# ATmga8_testBoard_v4.net
KiCad netlist of a schematic drawn in EAGLE
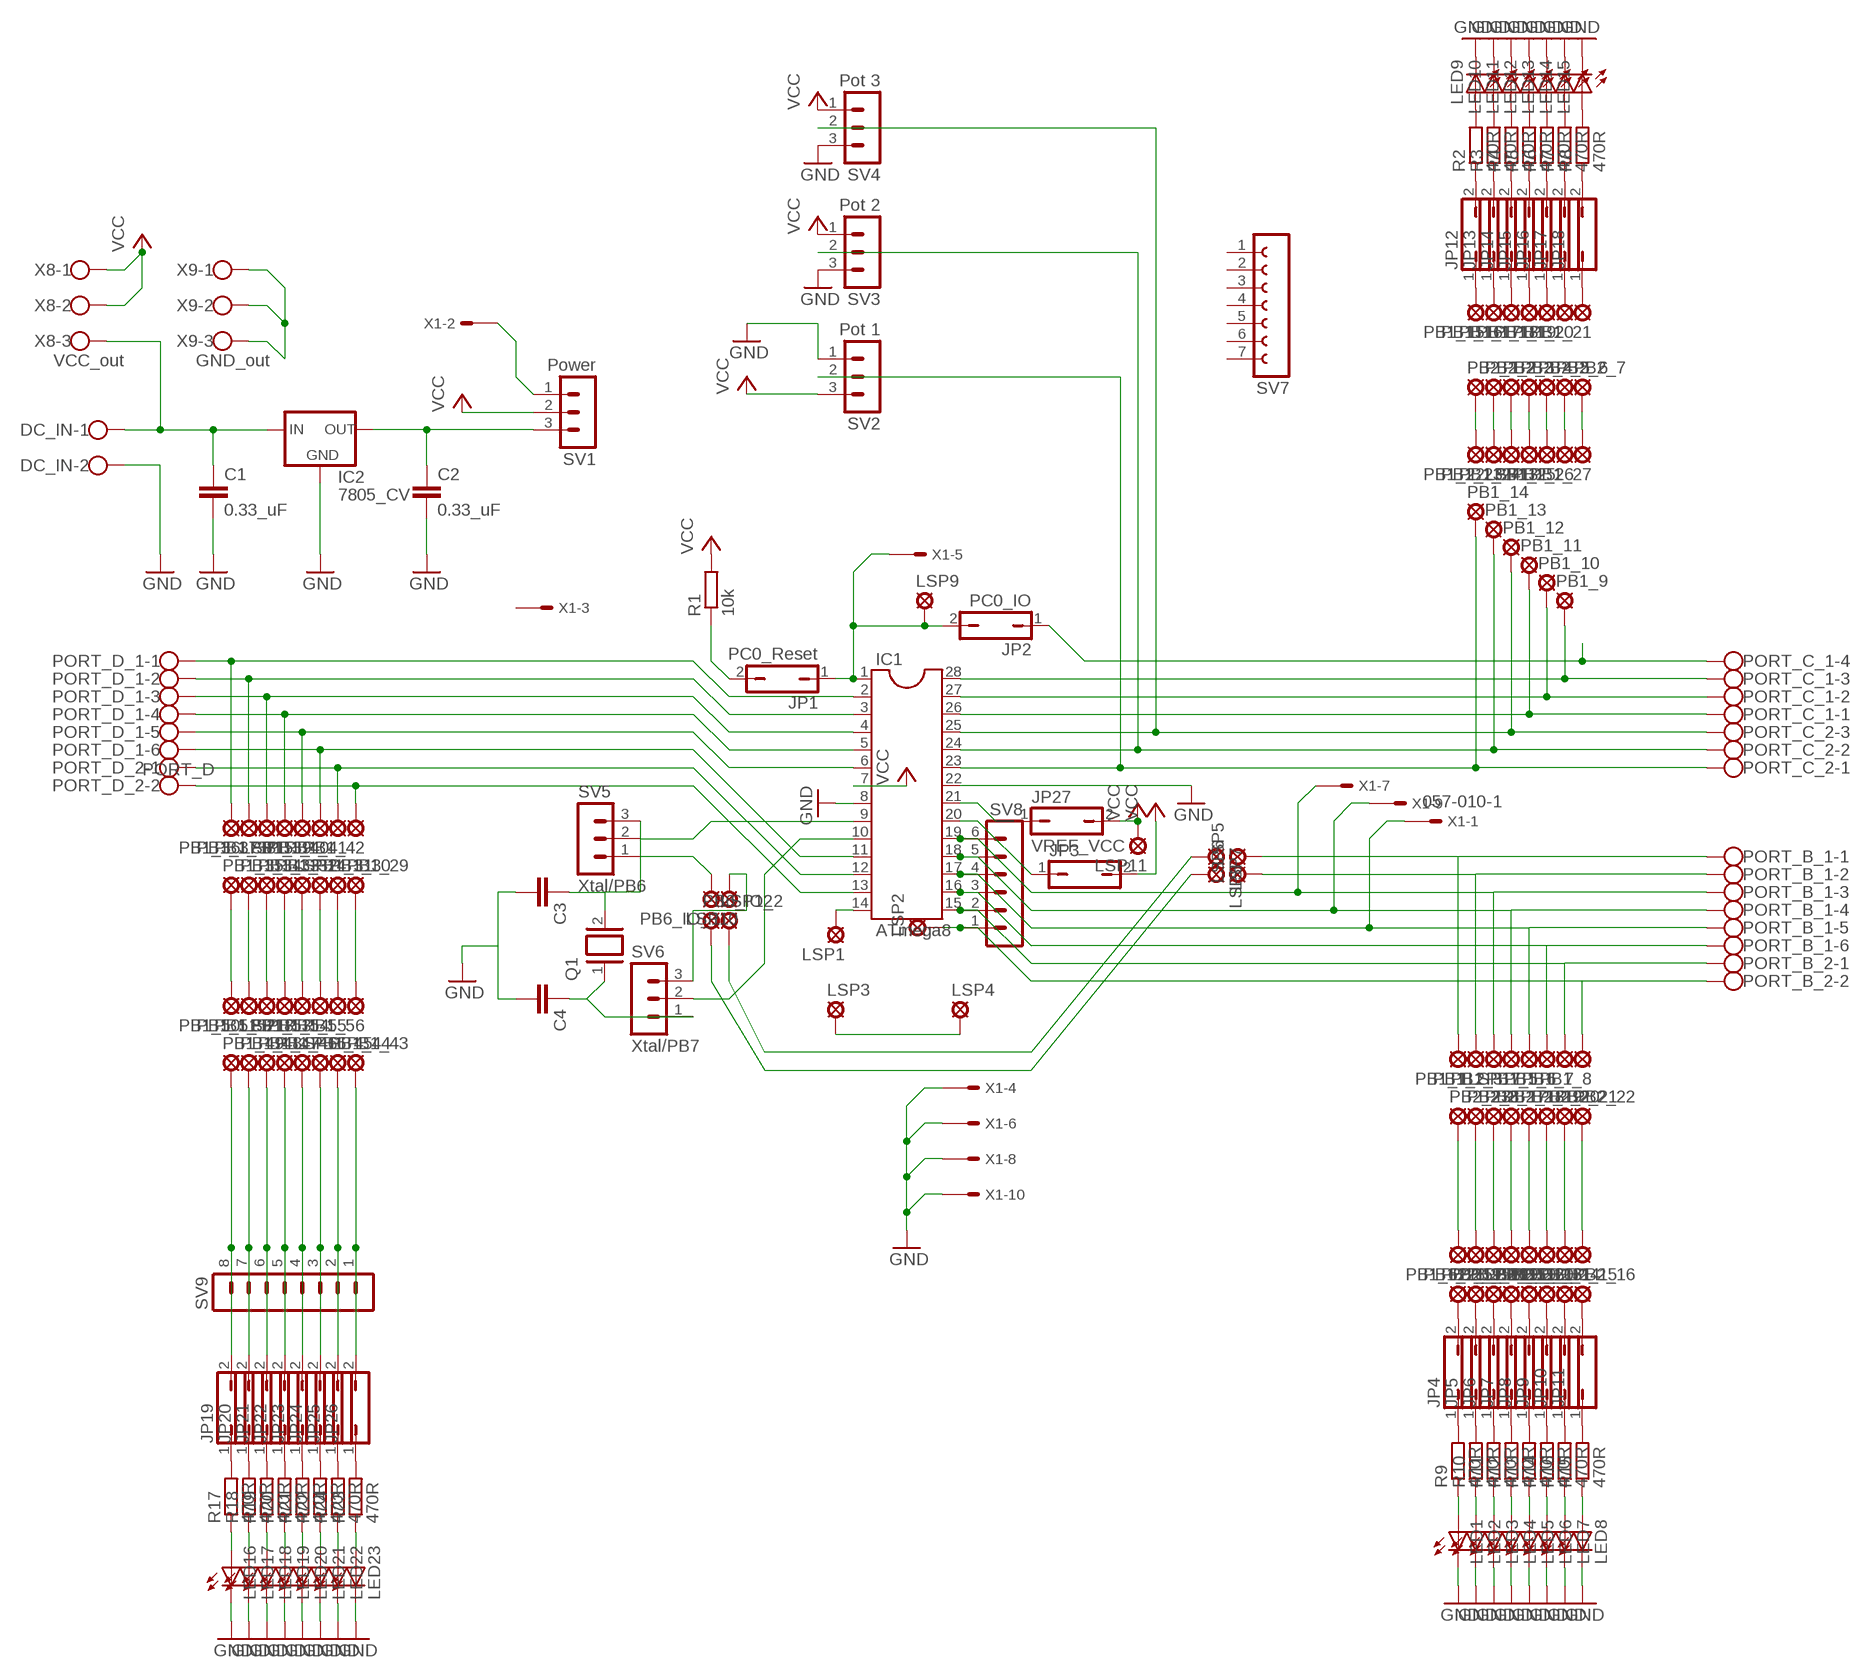
[diagram p0: schematic, sheet 1]

(export (version "E")
  (design (tool "Eeschema 10.0.6"))
  (components
    (comp (ref "C1")
      (value "0.33_uF")
      (footprint "eagle-import:C5B2.5")
      (libsource (lib "eagle-import") (part "C5/2.5"))
    )
    (comp (ref "C2")
      (value "0.33_uF")
      (footprint "eagle-import:C5B2.5")
      (libsource (lib "eagle-import") (part "C5/2.5"))
    )
    (comp (ref "C3")
      (value "C-EU025-024X044")
      (footprint "eagle-import:C025-024X044")
      (libsource (lib "eagle-import") (part "C-EU025-024X044"))
    )
    (comp (ref "C4")
      (value "C-EU025-024X044")
      (footprint "eagle-import:C025-024X044")
      (libsource (lib "eagle-import") (part "C-EU025-024X044"))
    )
    (comp (ref "DC_IN")
      (value "W237-102")
      (footprint "eagle-import:W237-102")
      (fields (field (name "MPN") "237-102"))
      (libsource (lib "eagle-import") (part "W237-102"))
    )
    (comp (ref "IC1")
      (value "ATmega8")
      (footprint "eagle-import:DIL28-3")
      (libsource (lib "eagle-import") (part "DIL28-3"))
    )
    (comp (ref "IC2")
      (value "7805_CV")
      (footprint "eagle-import:78XXS")
      (libsource (lib "eagle-import") (part "78XXS"))
    )
    (comp (ref "JP1")
      (value "PC0_Reset")
      (footprint "eagle-import:JP1")
      (libsource (lib "eagle-import") (part "JP1Q"))
    )
    (comp (ref "JP2")
      (value "PC0_IO")
      (footprint "eagle-import:JP1")
      (libsource (lib "eagle-import") (part "JP1Q"))
    )
    (comp (ref "JP3")
      (value "JP1Q")
      (footprint "eagle-import:JP1")
      (libsource (lib "eagle-import") (part "JP1Q"))
    )
    (comp (ref "JP4")
      (value "JP1Q")
      (footprint "eagle-import:JP1")
      (libsource (lib "eagle-import") (part "JP1Q"))
    )
    (comp (ref "JP5")
      (value "JP1Q")
      (footprint "eagle-import:JP1")
      (libsource (lib "eagle-import") (part "JP1Q"))
    )
    (comp (ref "JP6")
      (value "JP1Q")
      (footprint "eagle-import:JP1")
      (libsource (lib "eagle-import") (part "JP1Q"))
    )
    (comp (ref "JP7")
      (value "JP1Q")
      (footprint "eagle-import:JP1")
      (libsource (lib "eagle-import") (part "JP1Q"))
    )
    (comp (ref "JP8")
      (value "JP1Q")
      (footprint "eagle-import:JP1")
      (libsource (lib "eagle-import") (part "JP1Q"))
    )
    (comp (ref "JP9")
      (value "JP1Q")
      (footprint "eagle-import:JP1")
      (libsource (lib "eagle-import") (part "JP1Q"))
    )
    (comp (ref "JP10")
      (value "JP1Q")
      (footprint "eagle-import:JP1")
      (libsource (lib "eagle-import") (part "JP1Q"))
    )
    (comp (ref "JP11")
      (value "JP1Q")
      (footprint "eagle-import:JP1")
      (libsource (lib "eagle-import") (part "JP1Q"))
    )
    (comp (ref "JP12")
      (value "JP1Q")
      (footprint "eagle-import:JP1")
      (libsource (lib "eagle-import") (part "JP1Q"))
    )
    (comp (ref "JP13")
      (value "JP1Q")
      (footprint "eagle-import:JP1")
      (libsource (lib "eagle-import") (part "JP1Q"))
    )
    (comp (ref "JP14")
      (value "JP1Q")
      (footprint "eagle-import:JP1")
      (libsource (lib "eagle-import") (part "JP1Q"))
    )
    (comp (ref "JP15")
      (value "JP1Q")
      (footprint "eagle-import:JP1")
      (libsource (lib "eagle-import") (part "JP1Q"))
    )
    (comp (ref "JP16")
      (value "JP1Q")
      (footprint "eagle-import:JP1")
      (libsource (lib "eagle-import") (part "JP1Q"))
    )
    (comp (ref "JP17")
      (value "JP1Q")
      (footprint "eagle-import:JP1")
      (libsource (lib "eagle-import") (part "JP1Q"))
    )
    (comp (ref "JP18")
      (value "JP1Q")
      (footprint "eagle-import:JP1")
      (libsource (lib "eagle-import") (part "JP1Q"))
    )
    (comp (ref "JP19")
      (value "JP1Q")
      (footprint "eagle-import:JP1")
      (libsource (lib "eagle-import") (part "JP1Q"))
    )
    (comp (ref "JP20")
      (value "JP1Q")
      (footprint "eagle-import:JP1")
      (libsource (lib "eagle-import") (part "JP1Q"))
    )
    (comp (ref "JP21")
      (value "JP1Q")
      (footprint "eagle-import:JP1")
      (libsource (lib "eagle-import") (part "JP1Q"))
    )
    (comp (ref "JP22")
      (value "JP1Q")
      (footprint "eagle-import:JP1")
      (libsource (lib "eagle-import") (part "JP1Q"))
    )
    (comp (ref "JP23")
      (value "JP1Q")
      (footprint "eagle-import:JP1")
      (libsource (lib "eagle-import") (part "JP1Q"))
    )
    (comp (ref "JP24")
      (value "JP1Q")
      (footprint "eagle-import:JP1")
      (libsource (lib "eagle-import") (part "JP1Q"))
    )
    (comp (ref "JP25")
      (value "JP1Q")
      (footprint "eagle-import:JP1")
      (libsource (lib "eagle-import") (part "JP1Q"))
    )
    (comp (ref "JP26")
      (value "JP1Q")
      (footprint "eagle-import:JP1")
      (libsource (lib "eagle-import") (part "JP1Q"))
    )
    (comp (ref "JP27")
      (value "VREF_VCC")
      (footprint "eagle-import:JP1")
      (libsource (lib "eagle-import") (part "JP1Q"))
    )
    (comp (ref "LED1")
      (value "LED3MM")
      (footprint "eagle-import:LED3MM")
      (libsource (lib "eagle-import") (part "LED3MM"))
    )
    (comp (ref "LED2")
      (value "LED3MM")
      (footprint "eagle-import:LED3MM")
      (libsource (lib "eagle-import") (part "LED3MM"))
    )
    (comp (ref "LED3")
      (value "LED3MM")
      (footprint "eagle-import:LED3MM")
      (libsource (lib "eagle-import") (part "LED3MM"))
    )
    (comp (ref "LED4")
      (value "LED3MM")
      (footprint "eagle-import:LED3MM")
      (libsource (lib "eagle-import") (part "LED3MM"))
    )
    (comp (ref "LED5")
      (value "LED3MM")
      (footprint "eagle-import:LED3MM")
      (libsource (lib "eagle-import") (part "LED3MM"))
    )
    (comp (ref "LED6")
      (value "LED3MM")
      (footprint "eagle-import:LED3MM")
      (libsource (lib "eagle-import") (part "LED3MM"))
    )
    (comp (ref "LED7")
      (value "LED3MM")
      (footprint "eagle-import:LED3MM")
      (libsource (lib "eagle-import") (part "LED3MM"))
    )
    (comp (ref "LED8")
      (value "LED3MM")
      (footprint "eagle-import:LED3MM")
      (libsource (lib "eagle-import") (part "LED3MM"))
    )
    (comp (ref "LED9")
      (value "LED3MM")
      (footprint "eagle-import:LED3MM")
      (libsource (lib "eagle-import") (part "LED3MM"))
    )
    (comp (ref "LED10")
      (value "LED3MM")
      (footprint "eagle-import:LED3MM")
      (libsource (lib "eagle-import") (part "LED3MM"))
    )
    (comp (ref "LED11")
      (value "LED3MM")
      (footprint "eagle-import:LED3MM")
      (libsource (lib "eagle-import") (part "LED3MM"))
    )
    (comp (ref "LED12")
      (value "LED3MM")
      (footprint "eagle-import:LED3MM")
      (libsource (lib "eagle-import") (part "LED3MM"))
    )
    (comp (ref "LED13")
      (value "LED3MM")
      (footprint "eagle-import:LED3MM")
      (libsource (lib "eagle-import") (part "LED3MM"))
    )
    (comp (ref "LED14")
      (value "LED3MM")
      (footprint "eagle-import:LED3MM")
      (libsource (lib "eagle-import") (part "LED3MM"))
    )
    (comp (ref "LED15")
      (value "LED3MM")
      (footprint "eagle-import:LED3MM")
      (libsource (lib "eagle-import") (part "LED3MM"))
    )
    (comp (ref "LED16")
      (value "LED3MM")
      (footprint "eagle-import:LED3MM")
      (libsource (lib "eagle-import") (part "LED3MM"))
    )
    (comp (ref "LED17")
      (value "LED3MM")
      (footprint "eagle-import:LED3MM")
      (libsource (lib "eagle-import") (part "LED3MM"))
    )
    (comp (ref "LED18")
      (value "LED3MM")
      (footprint "eagle-import:LED3MM")
      (libsource (lib "eagle-import") (part "LED3MM"))
    )
    (comp (ref "LED19")
      (value "LED3MM")
      (footprint "eagle-import:LED3MM")
      (libsource (lib "eagle-import") (part "LED3MM"))
    )
    (comp (ref "LED20")
      (value "LED3MM")
      (footprint "eagle-import:LED3MM")
      (libsource (lib "eagle-import") (part "LED3MM"))
    )
    (comp (ref "LED21")
      (value "LED3MM")
      (footprint "eagle-import:LED3MM")
      (libsource (lib "eagle-import") (part "LED3MM"))
    )
    (comp (ref "LED22")
      (value "LED3MM")
      (footprint "eagle-import:LED3MM")
      (libsource (lib "eagle-import") (part "LED3MM"))
    )
    (comp (ref "LED23")
      (value "LED3MM")
      (footprint "eagle-import:LED3MM")
      (libsource (lib "eagle-import") (part "LED3MM"))
    )
    (comp (ref "LSP1")
      (value "LSP10")
      (footprint "eagle-import:LSP10")
      (libsource (lib "eagle-import") (part "LSP10"))
    )
    (comp (ref "LSP2")
      (value "LSP10")
      (footprint "eagle-import:LSP10")
      (libsource (lib "eagle-import") (part "LSP10"))
    )
    (comp (ref "LSP3")
      (value "LSP10")
      (footprint "eagle-import:LSP10")
      (libsource (lib "eagle-import") (part "LSP10"))
    )
    (comp (ref "LSP4")
      (value "LSP10")
      (footprint "eagle-import:LSP10")
      (libsource (lib "eagle-import") (part "LSP10"))
    )
    (comp (ref "LSP5")
      (value "LSP10")
      (footprint "eagle-import:LSP10")
      (libsource (lib "eagle-import") (part "LSP10"))
    )
    (comp (ref "LSP6")
      (value "LSP10")
      (footprint "eagle-import:LSP10")
      (libsource (lib "eagle-import") (part "LSP10"))
    )
    (comp (ref "LSP7")
      (value "LSP10")
      (footprint "eagle-import:LSP10")
      (libsource (lib "eagle-import") (part "LSP10"))
    )
    (comp (ref "LSP8")
      (value "LSP10")
      (footprint "eagle-import:LSP10")
      (libsource (lib "eagle-import") (part "LSP10"))
    )
    (comp (ref "LSP9")
      (value "LSP10")
      (footprint "eagle-import:LSP10")
      (libsource (lib "eagle-import") (part "LSP10"))
    )
    (comp (ref "LSP10")
      (value "LSP10")
      (footprint "eagle-import:LSP10")
      (libsource (lib "eagle-import") (part "LSP10"))
    )
    (comp (ref "LSP11")
      (value "LSP10")
      (footprint "eagle-import:LSP10")
      (libsource (lib "eagle-import") (part "LSP10"))
    )
    (comp (ref "LSP12")
      (value "LSP10")
      (footprint "eagle-import:LSP10")
      (libsource (lib "eagle-import") (part "LSP10"))
    )
    (comp (ref "LSP13")
      (value "LSP10")
      (footprint "eagle-import:LSP10")
      (libsource (lib "eagle-import") (part "LSP10"))
    )
    (comp (ref "LSP14")
      (value "LSP10")
      (footprint "eagle-import:LSP10")
      (libsource (lib "eagle-import") (part "LSP10"))
    )
    (comp (ref "LSP15")
      (value "LSP10")
      (footprint "eagle-import:LSP10")
      (libsource (lib "eagle-import") (part "LSP10"))
    )
    (comp (ref "LSP16")
      (value "LSP10")
      (footprint "eagle-import:LSP10")
      (libsource (lib "eagle-import") (part "LSP10"))
    )
    (comp (ref "LSP17")
      (value "LSP10")
      (footprint "eagle-import:LSP10")
      (libsource (lib "eagle-import") (part "LSP10"))
    )
    (comp (ref "LSP18")
      (value "LSP10")
      (footprint "eagle-import:LSP10")
      (libsource (lib "eagle-import") (part "LSP10"))
    )
    (comp (ref "LSP19")
      (value "LSP10")
      (footprint "eagle-import:LSP10")
      (libsource (lib "eagle-import") (part "LSP10"))
    )
    (comp (ref "PB1_1")
      (value "LSP10")
      (footprint "eagle-import:LSP10")
      (libsource (lib "eagle-import") (part "LSP10"))
    )
    (comp (ref "PB1_2")
      (value "LSP10")
      (footprint "eagle-import:LSP10")
      (libsource (lib "eagle-import") (part "LSP10"))
    )
    (comp (ref "PB1_3")
      (value "LSP10")
      (footprint "eagle-import:LSP10")
      (libsource (lib "eagle-import") (part "LSP10"))
    )
    (comp (ref "PB1_5")
      (value "LSP10")
      (footprint "eagle-import:LSP10")
      (libsource (lib "eagle-import") (part "LSP10"))
    )
    (comp (ref "PB1_6")
      (value "LSP10")
      (footprint "eagle-import:LSP10")
      (libsource (lib "eagle-import") (part "LSP10"))
    )
    (comp (ref "PB1_7")
      (value "LSP10")
      (footprint "eagle-import:LSP10")
      (libsource (lib "eagle-import") (part "LSP10"))
    )
    (comp (ref "PB1_8")
      (value "LSP10")
      (footprint "eagle-import:LSP10")
      (libsource (lib "eagle-import") (part "LSP10"))
    )
    (comp (ref "PB1_9")
      (value "LSP10")
      (footprint "eagle-import:LSP10")
      (libsource (lib "eagle-import") (part "LSP10"))
    )
    (comp (ref "PB1_10")
      (value "LSP10")
      (footprint "eagle-import:LSP10")
      (libsource (lib "eagle-import") (part "LSP10"))
    )
    (comp (ref "PB1_11")
      (value "LSP10")
      (footprint "eagle-import:LSP10")
      (libsource (lib "eagle-import") (part "LSP10"))
    )
    (comp (ref "PB1_12")
      (value "LSP10")
      (footprint "eagle-import:LSP10")
      (libsource (lib "eagle-import") (part "LSP10"))
    )
    (comp (ref "PB1_13")
      (value "LSP10")
      (footprint "eagle-import:LSP10")
      (libsource (lib "eagle-import") (part "LSP10"))
    )
    (comp (ref "PB1_14")
      (value "LSP10")
      (footprint "eagle-import:LSP10")
      (libsource (lib "eagle-import") (part "LSP10"))
    )
    (comp (ref "PB1_15")
      (value "LSP10")
      (footprint "eagle-import:LSP10")
      (libsource (lib "eagle-import") (part "LSP10"))
    )
    (comp (ref "PB1_16")
      (value "LSP10")
      (footprint "eagle-import:LSP10")
      (libsource (lib "eagle-import") (part "LSP10"))
    )
    (comp (ref "PB1_17")
      (value "LSP10")
      (footprint "eagle-import:LSP10")
      (libsource (lib "eagle-import") (part "LSP10"))
    )
    (comp (ref "PB1_18")
      (value "LSP10")
      (footprint "eagle-import:LSP10")
      (libsource (lib "eagle-import") (part "LSP10"))
    )
    (comp (ref "PB1_19")
      (value "LSP10")
      (footprint "eagle-import:LSP10")
      (libsource (lib "eagle-import") (part "LSP10"))
    )
    (comp (ref "PB1_20")
      (value "LSP10")
      (footprint "eagle-import:LSP10")
      (libsource (lib "eagle-import") (part "LSP10"))
    )
    (comp (ref "PB1_21")
      (value "LSP10")
      (footprint "eagle-import:LSP10")
      (libsource (lib "eagle-import") (part "LSP10"))
    )
    (comp (ref "PB1_22")
      (value "LSP10")
      (footprint "eagle-import:LSP10")
      (libsource (lib "eagle-import") (part "LSP10"))
    )
    (comp (ref "PB1_23")
      (value "LSP10")
      (footprint "eagle-import:LSP10")
      (libsource (lib "eagle-import") (part "LSP10"))
    )
    (comp (ref "PB1_24")
      (value "LSP10")
      (footprint "eagle-import:LSP10")
      (libsource (lib "eagle-import") (part "LSP10"))
    )
    (comp (ref "PB1_25")
      (value "LSP10")
      (footprint "eagle-import:LSP10")
      (libsource (lib "eagle-import") (part "LSP10"))
    )
    (comp (ref "PB1_26")
      (value "LSP10")
      (footprint "eagle-import:LSP10")
      (libsource (lib "eagle-import") (part "LSP10"))
    )
    (comp (ref "PB1_27")
      (value "LSP10")
      (footprint "eagle-import:LSP10")
      (libsource (lib "eagle-import") (part "LSP10"))
    )
    (comp (ref "PB1_28")
      (value "LSP10")
      (footprint "eagle-import:LSP10")
      (libsource (lib "eagle-import") (part "LSP10"))
    )
    (comp (ref "PB1_29")
      (value "LSP10")
      (footprint "eagle-import:LSP10")
      (libsource (lib "eagle-import") (part "LSP10"))
    )
    (comp (ref "PB1_30")
      (value "LSP10")
      (footprint "eagle-import:LSP10")
      (libsource (lib "eagle-import") (part "LSP10"))
    )
    (comp (ref "PB1_31")
      (value "LSP10")
      (footprint "eagle-import:LSP10")
      (libsource (lib "eagle-import") (part "LSP10"))
    )
    (comp (ref "PB1_32")
      (value "LSP10")
      (footprint "eagle-import:LSP10")
      (libsource (lib "eagle-import") (part "LSP10"))
    )
    (comp (ref "PB1_33")
      (value "LSP10")
      (footprint "eagle-import:LSP10")
      (libsource (lib "eagle-import") (part "LSP10"))
    )
    (comp (ref "PB1_34")
      (value "LSP10")
      (footprint "eagle-import:LSP10")
      (libsource (lib "eagle-import") (part "LSP10"))
    )
    (comp (ref "PB1_35")
      (value "LSP10")
      (footprint "eagle-import:LSP10")
      (libsource (lib "eagle-import") (part "LSP10"))
    )
    (comp (ref "PB1_36")
      (value "LSP10")
      (footprint "eagle-import:LSP10")
      (libsource (lib "eagle-import") (part "LSP10"))
    )
    (comp (ref "PB1_37")
      (value "LSP10")
      (footprint "eagle-import:LSP10")
      (libsource (lib "eagle-import") (part "LSP10"))
    )
    (comp (ref "PB1_38")
      (value "LSP10")
      (footprint "eagle-import:LSP10")
      (libsource (lib "eagle-import") (part "LSP10"))
    )
    (comp (ref "PB1_39")
      (value "LSP10")
      (footprint "eagle-import:LSP10")
      (libsource (lib "eagle-import") (part "LSP10"))
    )
    (comp (ref "PB1_40")
      (value "LSP10")
      (footprint "eagle-import:LSP10")
      (libsource (lib "eagle-import") (part "LSP10"))
    )
    (comp (ref "PB1_41")
      (value "LSP10")
      (footprint "eagle-import:LSP10")
      (libsource (lib "eagle-import") (part "LSP10"))
    )
    (comp (ref "PB1_42")
      (value "LSP10")
      (footprint "eagle-import:LSP10")
      (libsource (lib "eagle-import") (part "LSP10"))
    )
    (comp (ref "PB1_43")
      (value "LSP10")
      (footprint "eagle-import:LSP10")
      (libsource (lib "eagle-import") (part "LSP10"))
    )
    (comp (ref "PB1_44")
      (value "LSP10")
      (footprint "eagle-import:LSP10")
      (libsource (lib "eagle-import") (part "LSP10"))
    )
    (comp (ref "PB1_45")
      (value "LSP10")
      (footprint "eagle-import:LSP10")
      (libsource (lib "eagle-import") (part "LSP10"))
    )
    (comp (ref "PB1_46")
      (value "LSP10")
      (footprint "eagle-import:LSP10")
      (libsource (lib "eagle-import") (part "LSP10"))
    )
    (comp (ref "PB1_47")
      (value "LSP10")
      (footprint "eagle-import:LSP10")
      (libsource (lib "eagle-import") (part "LSP10"))
    )
    (comp (ref "PB1_48")
      (value "LSP10")
      (footprint "eagle-import:LSP10")
      (libsource (lib "eagle-import") (part "LSP10"))
    )
    (comp (ref "PB1_49")
      (value "LSP10")
      (footprint "eagle-import:LSP10")
      (libsource (lib "eagle-import") (part "LSP10"))
    )
    (comp (ref "PB1_50")
      (value "LSP10")
      (footprint "eagle-import:LSP10")
      (libsource (lib "eagle-import") (part "LSP10"))
    )
    (comp (ref "PB1_51")
      (value "LSP10")
      (footprint "eagle-import:LSP10")
      (libsource (lib "eagle-import") (part "LSP10"))
    )
    (comp (ref "PB1_52")
      (value "LSP10")
      (footprint "eagle-import:LSP10")
      (libsource (lib "eagle-import") (part "LSP10"))
    )
    (comp (ref "PB1_53")
      (value "LSP10")
      (footprint "eagle-import:LSP10")
      (libsource (lib "eagle-import") (part "LSP10"))
    )
    (comp (ref "PB1_54")
      (value "LSP10")
      (footprint "eagle-import:LSP10")
      (libsource (lib "eagle-import") (part "LSP10"))
    )
    (comp (ref "PB1_55")
      (value "LSP10")
      (footprint "eagle-import:LSP10")
      (libsource (lib "eagle-import") (part "LSP10"))
    )
    (comp (ref "PB1_56")
      (value "LSP10")
      (footprint "eagle-import:LSP10")
      (libsource (lib "eagle-import") (part "LSP10"))
    )
    (comp (ref "PB1_57")
      (value "LSP10")
      (footprint "eagle-import:LSP10")
      (libsource (lib "eagle-import") (part "LSP10"))
    )
    (comp (ref "PB1_58")
      (value "LSP10")
      (footprint "eagle-import:LSP10")
      (libsource (lib "eagle-import") (part "LSP10"))
    )
    (comp (ref "PB1_59")
      (value "LSP10")
      (footprint "eagle-import:LSP10")
      (libsource (lib "eagle-import") (part "LSP10"))
    )
    (comp (ref "PB1_60")
      (value "LSP10")
      (footprint "eagle-import:LSP10")
      (libsource (lib "eagle-import") (part "LSP10"))
    )
    (comp (ref "PB1_61")
      (value "LSP10")
      (footprint "eagle-import:LSP10")
      (libsource (lib "eagle-import") (part "LSP10"))
    )
    (comp (ref "PB1_62")
      (value "LSP10")
      (footprint "eagle-import:LSP10")
      (libsource (lib "eagle-import") (part "LSP10"))
    )
    (comp (ref "PB2_1")
      (value "LSP10")
      (footprint "eagle-import:LSP10")
      (libsource (lib "eagle-import") (part "LSP10"))
    )
    (comp (ref "PB2_2")
      (value "LSP10")
      (footprint "eagle-import:LSP10")
      (libsource (lib "eagle-import") (part "LSP10"))
    )
    (comp (ref "PB2_3")
      (value "LSP10")
      (footprint "eagle-import:LSP10")
      (libsource (lib "eagle-import") (part "LSP10"))
    )
    (comp (ref "PB2_4")
      (value "LSP10")
      (footprint "eagle-import:LSP10")
      (libsource (lib "eagle-import") (part "LSP10"))
    )
    (comp (ref "PB2_5")
      (value "LSP10")
      (footprint "eagle-import:LSP10")
      (libsource (lib "eagle-import") (part "LSP10"))
    )
    (comp (ref "PB2_6")
      (value "LSP10")
      (footprint "eagle-import:LSP10")
      (libsource (lib "eagle-import") (part "LSP10"))
    )
    (comp (ref "PB2_7")
      (value "LSP10")
      (footprint "eagle-import:LSP10")
      (libsource (lib "eagle-import") (part "LSP10"))
    )
    (comp (ref "PB2_8")
      (value "LSP10")
      (footprint "eagle-import:LSP10")
      (libsource (lib "eagle-import") (part "LSP10"))
    )
    (comp (ref "PB2_9")
      (value "LSP10")
      (footprint "eagle-import:LSP10")
      (libsource (lib "eagle-import") (part "LSP10"))
    )
    (comp (ref "PB2_10")
      (value "LSP10")
      (footprint "eagle-import:LSP10")
      (libsource (lib "eagle-import") (part "LSP10"))
    )
    (comp (ref "PB2_11")
      (value "LSP10")
      (footprint "eagle-import:LSP10")
      (libsource (lib "eagle-import") (part "LSP10"))
    )
    (comp (ref "PB2_12")
      (value "LSP10")
      (footprint "eagle-import:LSP10")
      (libsource (lib "eagle-import") (part "LSP10"))
    )
    (comp (ref "PB2_13")
      (value "LSP10")
      (footprint "eagle-import:LSP10")
      (libsource (lib "eagle-import") (part "LSP10"))
    )
    (comp (ref "PB2_14")
      (value "LSP10")
      (footprint "eagle-import:LSP10")
      (libsource (lib "eagle-import") (part "LSP10"))
    )
    (comp (ref "PB2_15")
      (value "LSP10")
      (footprint "eagle-import:LSP10")
      (libsource (lib "eagle-import") (part "LSP10"))
    )
    (comp (ref "PB2_16")
      (value "LSP10")
      (footprint "eagle-import:LSP10")
      (libsource (lib "eagle-import") (part "LSP10"))
    )
    (comp (ref "PB2_17")
      (value "LSP10")
      (footprint "eagle-import:LSP10")
      (libsource (lib "eagle-import") (part "LSP10"))
    )
    (comp (ref "PB2_18")
      (value "LSP10")
      (footprint "eagle-import:LSP10")
      (libsource (lib "eagle-import") (part "LSP10"))
    )
    (comp (ref "PB2_19")
      (value "LSP10")
      (footprint "eagle-import:LSP10")
      (libsource (lib "eagle-import") (part "LSP10"))
    )
    (comp (ref "PB2_20")
      (value "LSP10")
      (footprint "eagle-import:LSP10")
      (libsource (lib "eagle-import") (part "LSP10"))
    )
    (comp (ref "PB2_21")
      (value "LSP10")
      (footprint "eagle-import:LSP10")
      (libsource (lib "eagle-import") (part "LSP10"))
    )
    (comp (ref "PB2_22")
      (value "LSP10")
      (footprint "eagle-import:LSP10")
      (libsource (lib "eagle-import") (part "LSP10"))
    )
    (comp (ref "PB2_23")
      (value "LSP10")
      (footprint "eagle-import:LSP10")
      (libsource (lib "eagle-import") (part "LSP10"))
    )
    (comp (ref "PB6_IO_1")
      (value "LSP10")
      (footprint "eagle-import:LSP10")
      (libsource (lib "eagle-import") (part "LSP10"))
    )
    (comp (ref "PB6_IO_2")
      (value "LSP10")
      (footprint "eagle-import:LSP10")
      (libsource (lib "eagle-import") (part "LSP10"))
    )
    (comp (ref "PORT_B_1")
      (value "W237-6")
      (footprint "eagle-import:W237-6")
      (libsource (lib "eagle-import") (part "W237-6"))
    )
    (comp (ref "PORT_B_2")
      (value "W237-102")
      (footprint "eagle-import:W237-102")
      (fields (field (name "MPN") "237-102"))
      (libsource (lib "eagle-import") (part "W237-102"))
    )
    (comp (ref "PORT_C_1")
      (value "W237-4")
      (footprint "eagle-import:W237-4")
      (libsource (lib "eagle-import") (part "W237-4"))
    )
    (comp (ref "PORT_C_2")
      (value "W237-103")
      (footprint "eagle-import:W237-103")
      (fields (field (name "MPN") "237-103"))
      (libsource (lib "eagle-import") (part "W237-103"))
    )
    (comp (ref "PORT_D_1")
      (value "PORT_D")
      (footprint "eagle-import:W237-6")
      (libsource (lib "eagle-import") (part "W237-6"))
    )
    (comp (ref "PORT_D_2")
      (value "W237-102")
      (footprint "eagle-import:W237-102")
      (fields (field (name "MPN") "237-102"))
      (libsource (lib "eagle-import") (part "W237-102"))
    )
    (comp (ref "Q1")
      (value "XTAL")
      (footprint "eagle-import:Q")
      (libsource (lib "eagle-import") (part "XTAL"))
    )
    (comp (ref "R1")
      (value "10k")
      (footprint "eagle-import:0204_7")
      (libsource (lib "eagle-import") (part "resistor_R-EU_0204/7"))
    )
    (comp (ref "R2")
      (value "470R")
      (footprint "eagle-import:0207_7")
      (libsource (lib "eagle-import") (part "R-EU_0207/7"))
    )
    (comp (ref "R3")
      (value "470R")
      (footprint "eagle-import:0207_7")
      (libsource (lib "eagle-import") (part "R-EU_0207/7"))
    )
    (comp (ref "R4")
      (value "470R")
      (footprint "eagle-import:0207_7")
      (libsource (lib "eagle-import") (part "R-EU_0207/7"))
    )
    (comp (ref "R5")
      (value "470R")
      (footprint "eagle-import:0207_7")
      (libsource (lib "eagle-import") (part "R-EU_0207/7"))
    )
    (comp (ref "R6")
      (value "470R")
      (footprint "eagle-import:0207_7")
      (libsource (lib "eagle-import") (part "R-EU_0207/7"))
    )
    (comp (ref "R7")
      (value "470R")
      (footprint "eagle-import:0207_7")
      (libsource (lib "eagle-import") (part "R-EU_0207/7"))
    )
    (comp (ref "R8")
      (value "470R")
      (footprint "eagle-import:0207_7")
      (libsource (lib "eagle-import") (part "R-EU_0207/7"))
    )
    (comp (ref "R9")
      (value "470R")
      (footprint "eagle-import:0207_7")
      (libsource (lib "eagle-import") (part "R-EU_0207/7"))
    )
    (comp (ref "R10")
      (value "470R")
      (footprint "eagle-import:0207_7")
      (libsource (lib "eagle-import") (part "R-EU_0207/7"))
    )
    (comp (ref "R11")
      (value "470R")
      (footprint "eagle-import:0207_7")
      (libsource (lib "eagle-import") (part "R-EU_0207/7"))
    )
    (comp (ref "R12")
      (value "470R")
      (footprint "eagle-import:0207_7")
      (libsource (lib "eagle-import") (part "R-EU_0207/7"))
    )
    (comp (ref "R13")
      (value "470R")
      (footprint "eagle-import:0207_7")
      (libsource (lib "eagle-import") (part "R-EU_0207/7"))
    )
    (comp (ref "R14")
      (value "470R")
      (footprint "eagle-import:0207_7")
      (libsource (lib "eagle-import") (part "R-EU_0207/7"))
    )
    (comp (ref "R15")
      (value "470R")
      (footprint "eagle-import:0207_7")
      (libsource (lib "eagle-import") (part "R-EU_0207/7"))
    )
    (comp (ref "R16")
      (value "470R")
      (footprint "eagle-import:0207_7")
      (libsource (lib "eagle-import") (part "R-EU_0207/7"))
    )
    (comp (ref "R17")
      (value "470R")
      (footprint "eagle-import:0207_7")
      (libsource (lib "eagle-import") (part "R-EU_0207/7"))
    )
    (comp (ref "R18")
      (value "470R")
      (footprint "eagle-import:0207_7")
      (libsource (lib "eagle-import") (part "R-EU_0207/7"))
    )
    (comp (ref "R19")
      (value "470R")
      (footprint "eagle-import:0207_7")
      (libsource (lib "eagle-import") (part "R-EU_0207/7"))
    )
    (comp (ref "R20")
      (value "470R")
      (footprint "eagle-import:0207_7")
      (libsource (lib "eagle-import") (part "R-EU_0207/7"))
    )
    (comp (ref "R21")
      (value "470R")
      (footprint "eagle-import:0207_7")
      (libsource (lib "eagle-import") (part "R-EU_0207/7"))
    )
    (comp (ref "R22")
      (value "470R")
      (footprint "eagle-import:0207_7")
      (libsource (lib "eagle-import") (part "R-EU_0207/7"))
    )
    (comp (ref "R23")
      (value "470R")
      (footprint "eagle-import:0207_7")
      (libsource (lib "eagle-import") (part "R-EU_0207/7"))
    )
    (comp (ref "R24")
      (value "470R")
      (footprint "eagle-import:0207_7")
      (libsource (lib "eagle-import") (part "R-EU_0207/7"))
    )
    (comp (ref "SV1")
      (value "Power")
      (footprint "eagle-import:MA03-1")
      (libsource (lib "eagle-import") (part "MA03-1"))
    )
    (comp (ref "SV2")
      (value "Pot 1")
      (footprint "eagle-import:MA03-1")
      (libsource (lib "eagle-import") (part "MA03-1"))
    )
    (comp (ref "SV3")
      (value "Pot 2")
      (footprint "eagle-import:MA03-1")
      (libsource (lib "eagle-import") (part "MA03-1"))
    )
    (comp (ref "SV4")
      (value "Pot 3")
      (footprint "eagle-import:MA03-1")
      (libsource (lib "eagle-import") (part "MA03-1"))
    )
    (comp (ref "SV5")
      (value "Xtal/PB6")
      (footprint "eagle-import:MA03-1")
      (libsource (lib "eagle-import") (part "MA03-1"))
    )
    (comp (ref "SV6")
      (value "Xtal/PB7")
      (footprint "eagle-import:MA03-1")
      (libsource (lib "eagle-import") (part "MA03-1"))
    )
    (comp (ref "SV7")
      (value "FE07-1")
      (footprint "eagle-import:FE07")
      (libsource (lib "eagle-import") (part "FE07-1"))
    )
    (comp (ref "SV8")
      (value "MA06-1")
      (footprint "eagle-import:MA06-1")
      (libsource (lib "eagle-import") (part "MA06-1"))
    )
    (comp (ref "SV9")
      (value "MA08-1")
      (footprint "eagle-import:MA08-1")
      (libsource (lib "eagle-import") (part "MA08-1"))
    )
    (comp (ref "X1")
      (value "057-010-1")
      (footprint "eagle-import:057-010-1")
      (libsource (lib "eagle-import") (part "057-010-1"))
    )
    (comp (ref "X8")
      (value "VCC_out")
      (footprint "eagle-import:W237-103")
      (fields (field (name "MPN") "237-103"))
      (libsource (lib "eagle-import") (part "W237-103"))
    )
    (comp (ref "X9")
      (value "GND_out")
      (footprint "eagle-import:W237-103")
      (fields (field (name "MPN") "237-103"))
      (libsource (lib "eagle-import") (part "W237-103"))
    )
  )
  (nets
    (net (code "1") (name "GND") (class "Default")
      (node (ref "C1") (pin "2") (pinfunction "2_2") (pintype "passive"))
      (node (ref "C2") (pin "2") (pinfunction "2_2") (pintype "passive"))
      (node (ref "C3") (pin "2") (pinfunction "2_2") (pintype "passive"))
      (node (ref "C4") (pin "2") (pinfunction "2_2") (pintype "passive"))
      (node (ref "DC_IN") (pin "2") (pinfunction "KL_2") (pintype "passive"))
      (node (ref "IC1") (pin "22") (pinfunction "22_22") (pintype "passive"))
      (node (ref "IC1") (pin "8") (pinfunction "8_8") (pintype "passive"))
      (node (ref "IC2") (pin "GND") (pinfunction "GND_GND") (pintype "input"))
      (node (ref "LED1") (pin "K") (pinfunction "C_K") (pintype "passive"))
      (node (ref "LED10") (pin "K") (pinfunction "C_K") (pintype "passive"))
      (node (ref "LED11") (pin "K") (pinfunction "C_K") (pintype "passive"))
      (node (ref "LED12") (pin "K") (pinfunction "C_K") (pintype "passive"))
      (node (ref "LED13") (pin "K") (pinfunction "C_K") (pintype "passive"))
      (node (ref "LED14") (pin "K") (pinfunction "C_K") (pintype "passive"))
      (node (ref "LED15") (pin "K") (pinfunction "C_K") (pintype "passive"))
      (node (ref "LED16") (pin "K") (pinfunction "C_K") (pintype "passive"))
      (node (ref "LED17") (pin "K") (pinfunction "C_K") (pintype "passive"))
      (node (ref "LED18") (pin "K") (pinfunction "C_K") (pintype "passive"))
      (node (ref "LED19") (pin "K") (pinfunction "C_K") (pintype "passive"))
      (node (ref "LED2") (pin "K") (pinfunction "C_K") (pintype "passive"))
      (node (ref "LED20") (pin "K") (pinfunction "C_K") (pintype "passive"))
      (node (ref "LED21") (pin "K") (pinfunction "C_K") (pintype "passive"))
      (node (ref "LED22") (pin "K") (pinfunction "C_K") (pintype "passive"))
      (node (ref "LED23") (pin "K") (pinfunction "C_K") (pintype "passive"))
      (node (ref "LED3") (pin "K") (pinfunction "C_K") (pintype "passive"))
      (node (ref "LED4") (pin "K") (pinfunction "C_K") (pintype "passive"))
      (node (ref "LED5") (pin "K") (pinfunction "C_K") (pintype "passive"))
      (node (ref "LED6") (pin "K") (pinfunction "C_K") (pintype "passive"))
      (node (ref "LED7") (pin "K") (pinfunction "C_K") (pintype "passive"))
      (node (ref "LED8") (pin "K") (pinfunction "C_K") (pintype "passive"))
      (node (ref "LED9") (pin "K") (pinfunction "C_K") (pintype "passive"))
      (node (ref "SV2") (pin "1") (pinfunction "1_1") (pintype "passive"))
      (node (ref "SV3") (pin "3") (pinfunction "3_3") (pintype "passive"))
      (node (ref "SV4") (pin "3") (pinfunction "3_3") (pintype "passive"))
      (node (ref "X1") (pin "10") (pinfunction "S_10") (pintype "passive"))
      (node (ref "X1") (pin "4") (pinfunction "S_4") (pintype "passive"))
      (node (ref "X1") (pin "6") (pinfunction "S_6") (pintype "passive"))
      (node (ref "X1") (pin "8") (pinfunction "S_8") (pintype "passive"))
    )
    (net (code "2") (name "Net-(C2-Pad1)") (class "Default")
      (node (ref "C2") (pin "1") (pinfunction "1_1") (pintype "passive"))
      (node (ref "IC2") (pin "OUT") (pinfunction "OUT_OUT") (pintype "passive"))
      (node (ref "SV1") (pin "3") (pinfunction "3_3") (pintype "passive"))
    )
    (net (code "3") (name "Net-(C3-Pad1)") (class "Default")
      (node (ref "C3") (pin "1") (pinfunction "1_1") (pintype "passive"))
      (node (ref "Q1") (pin "2") (pinfunction "2_2") (pintype "passive"))
      (node (ref "SV5") (pin "3") (pinfunction "3_3") (pintype "passive"))
    )
    (net (code "4") (name "Net-(C4-Pad1)") (class "Default")
      (node (ref "C4") (pin "1") (pinfunction "1_1") (pintype "passive"))
      (node (ref "Q1") (pin "1") (pinfunction "1_1") (pintype "passive"))
      (node (ref "SV6") (pin "1") (pinfunction "1_1") (pintype "passive"))
    )
    (net (code "5") (name "Net-(DC_INA-KL)") (class "Default")
      (node (ref "C1") (pin "1") (pinfunction "1_1") (pintype "passive"))
      (node (ref "DC_IN") (pin "1") (pinfunction "KL_1") (pintype "passive"))
      (node (ref "IC2") (pin "IN") (pinfunction "IN_IN") (pintype "input"))
      (node (ref "X8") (pin "3") (pinfunction "KL_3") (pintype "passive"))
    )
    (net (code "6") (name "Net-(IC1-Pad9)") (class "Default")
      (node (ref "IC1") (pin "9") (pinfunction "9_9") (pintype "passive"))
      (node (ref "SV5") (pin "2") (pinfunction "2_2") (pintype "passive"))
    )
    (net (code "7") (name "Net-(IC1-Pad10)") (class "Default")
      (node (ref "IC1") (pin "10") (pinfunction "10_10") (pintype "passive"))
      (node (ref "SV6") (pin "2") (pinfunction "2_2") (pintype "passive"))
    )
    (net (code "8") (name "Net-(IC1-Pad14)") (class "Default")
      (node (ref "IC1") (pin "14") (pinfunction "14_14") (pintype "passive"))
      (node (ref "LSP1") (pin "MP") (pinfunction "MP_MP") (pintype "passive"))
    )
    (net (code "9") (name "Net-(IC1-Pad20)") (class "Default")
      (node (ref "IC1") (pin "20") (pinfunction "20_20") (pintype "passive"))
      (node (ref "JP3") (pin "1") (pinfunction "1_1") (pintype "passive"))
    )
    (net (code "10") (name "Net-(IC1-Pad21)") (class "Default")
      (node (ref "IC1") (pin "21") (pinfunction "21_21") (pintype "passive"))
      (node (ref "JP27") (pin "1") (pinfunction "1_1") (pintype "passive"))
    )
    (net (code "11") (name "Net-(JP1-Pad2)") (class "Default")
      (node (ref "JP1") (pin "2") (pinfunction "2_2") (pintype "passive"))
      (node (ref "R1") (pin "1") (pinfunction "1_1") (pintype "passive"))
    )
    (net (code "12") (name "Net-(JP4-Pad1)") (class "Default")
      (node (ref "JP4") (pin "1") (pinfunction "1_1") (pintype "passive"))
      (node (ref "R9") (pin "2") (pinfunction "2_2") (pintype "passive"))
    )
    (net (code "13") (name "Net-(JP4-Pad2)") (class "Default")
      (node (ref "JP4") (pin "2") (pinfunction "2_2") (pintype "passive"))
      (node (ref "PB2_9") (pin "MP") (pinfunction "MP_MP") (pintype "passive"))
    )
    (net (code "14") (name "Net-(JP5-Pad1)") (class "Default")
      (node (ref "JP5") (pin "1") (pinfunction "1_1") (pintype "passive"))
      (node (ref "R10") (pin "2") (pinfunction "2_2") (pintype "passive"))
    )
    (net (code "15") (name "Net-(JP5-Pad2)") (class "Default")
      (node (ref "JP5") (pin "2") (pinfunction "2_2") (pintype "passive"))
      (node (ref "PB2_10") (pin "MP") (pinfunction "MP_MP") (pintype "passive"))
    )
    (net (code "16") (name "Net-(JP6-Pad1)") (class "Default")
      (node (ref "JP6") (pin "1") (pinfunction "1_1") (pintype "passive"))
      (node (ref "R11") (pin "2") (pinfunction "2_2") (pintype "passive"))
    )
    (net (code "17") (name "Net-(JP6-Pad2)") (class "Default")
      (node (ref "JP6") (pin "2") (pinfunction "2_2") (pintype "passive"))
      (node (ref "PB2_11") (pin "MP") (pinfunction "MP_MP") (pintype "passive"))
    )
    (net (code "18") (name "Net-(JP7-Pad1)") (class "Default")
      (node (ref "JP7") (pin "1") (pinfunction "1_1") (pintype "passive"))
      (node (ref "R12") (pin "2") (pinfunction "2_2") (pintype "passive"))
    )
    (net (code "19") (name "Net-(JP7-Pad2)") (class "Default")
      (node (ref "JP7") (pin "2") (pinfunction "2_2") (pintype "passive"))
      (node (ref "PB2_12") (pin "MP") (pinfunction "MP_MP") (pintype "passive"))
    )
    (net (code "20") (name "Net-(JP8-Pad1)") (class "Default")
      (node (ref "JP8") (pin "1") (pinfunction "1_1") (pintype "passive"))
      (node (ref "R13") (pin "2") (pinfunction "2_2") (pintype "passive"))
    )
    (net (code "21") (name "Net-(JP8-Pad2)") (class "Default")
      (node (ref "JP8") (pin "2") (pinfunction "2_2") (pintype "passive"))
      (node (ref "PB2_13") (pin "MP") (pinfunction "MP_MP") (pintype "passive"))
    )
    (net (code "22") (name "Net-(JP9-Pad1)") (class "Default")
      (node (ref "JP9") (pin "1") (pinfunction "1_1") (pintype "passive"))
      (node (ref "R14") (pin "2") (pinfunction "2_2") (pintype "passive"))
    )
    (net (code "23") (name "Net-(JP9-Pad2)") (class "Default")
      (node (ref "JP9") (pin "2") (pinfunction "2_2") (pintype "passive"))
      (node (ref "PB2_14") (pin "MP") (pinfunction "MP_MP") (pintype "passive"))
    )
    (net (code "24") (name "Net-(JP10-Pad1)") (class "Default")
      (node (ref "JP10") (pin "1") (pinfunction "1_1") (pintype "passive"))
      (node (ref "R16") (pin "2") (pinfunction "2_2") (pintype "passive"))
    )
    (net (code "25") (name "Net-(JP10-Pad2)") (class "Default")
      (node (ref "JP10") (pin "2") (pinfunction "2_2") (pintype "passive"))
      (node (ref "PB2_15") (pin "MP") (pinfunction "MP_MP") (pintype "passive"))
    )
    (net (code "26") (name "Net-(JP11-Pad1)") (class "Default")
      (node (ref "JP11") (pin "1") (pinfunction "1_1") (pintype "passive"))
      (node (ref "R15") (pin "2") (pinfunction "2_2") (pintype "passive"))
    )
    (net (code "27") (name "Net-(JP11-Pad2)") (class "Default")
      (node (ref "JP11") (pin "2") (pinfunction "2_2") (pintype "passive"))
      (node (ref "PB2_16") (pin "MP") (pinfunction "MP_MP") (pintype "passive"))
    )
    (net (code "28") (name "Net-(JP12-Pad1)") (class "Default")
      (node (ref "JP12") (pin "1") (pinfunction "1_1") (pintype "passive"))
      (node (ref "PB1_15") (pin "MP") (pinfunction "MP_MP") (pintype "passive"))
    )
    (net (code "29") (name "Net-(JP12-Pad2)") (class "Default")
      (node (ref "JP12") (pin "2") (pinfunction "2_2") (pintype "passive"))
      (node (ref "R2") (pin "1") (pinfunction "1_1") (pintype "passive"))
    )
    (net (code "30") (name "Net-(JP13-Pad1)") (class "Default")
      (node (ref "JP13") (pin "1") (pinfunction "1_1") (pintype "passive"))
      (node (ref "PB1_16") (pin "MP") (pinfunction "MP_MP") (pintype "passive"))
    )
    (net (code "31") (name "Net-(JP13-Pad2)") (class "Default")
      (node (ref "JP13") (pin "2") (pinfunction "2_2") (pintype "passive"))
      (node (ref "R3") (pin "1") (pinfunction "1_1") (pintype "passive"))
    )
    (net (code "32") (name "Net-(JP14-Pad1)") (class "Default")
      (node (ref "JP14") (pin "1") (pinfunction "1_1") (pintype "passive"))
      (node (ref "PB1_17") (pin "MP") (pinfunction "MP_MP") (pintype "passive"))
    )
    (net (code "33") (name "Net-(JP14-Pad2)") (class "Default")
      (node (ref "JP14") (pin "2") (pinfunction "2_2") (pintype "passive"))
      (node (ref "R4") (pin "1") (pinfunction "1_1") (pintype "passive"))
    )
    (net (code "34") (name "Net-(JP15-Pad1)") (class "Default")
      (node (ref "JP15") (pin "1") (pinfunction "1_1") (pintype "passive"))
      (node (ref "PB1_18") (pin "MP") (pinfunction "MP_MP") (pintype "passive"))
    )
    (net (code "35") (name "Net-(JP15-Pad2)") (class "Default")
      (node (ref "JP15") (pin "2") (pinfunction "2_2") (pintype "passive"))
      (node (ref "R5") (pin "1") (pinfunction "1_1") (pintype "passive"))
    )
    (net (code "36") (name "Net-(JP16-Pad1)") (class "Default")
      (node (ref "JP16") (pin "1") (pinfunction "1_1") (pintype "passive"))
      (node (ref "PB1_19") (pin "MP") (pinfunction "MP_MP") (pintype "passive"))
    )
    (net (code "37") (name "Net-(JP16-Pad2)") (class "Default")
      (node (ref "JP16") (pin "2") (pinfunction "2_2") (pintype "passive"))
      (node (ref "R6") (pin "1") (pinfunction "1_1") (pintype "passive"))
    )
    (net (code "38") (name "Net-(JP17-Pad1)") (class "Default")
      (node (ref "JP17") (pin "1") (pinfunction "1_1") (pintype "passive"))
      (node (ref "PB1_20") (pin "MP") (pinfunction "MP_MP") (pintype "passive"))
    )
    (net (code "39") (name "Net-(JP17-Pad2)") (class "Default")
      (node (ref "JP17") (pin "2") (pinfunction "2_2") (pintype "passive"))
      (node (ref "R7") (pin "1") (pinfunction "1_1") (pintype "passive"))
    )
    (net (code "40") (name "Net-(JP18-Pad1)") (class "Default")
      (node (ref "JP18") (pin "1") (pinfunction "1_1") (pintype "passive"))
      (node (ref "PB1_21") (pin "MP") (pinfunction "MP_MP") (pintype "passive"))
    )
    (net (code "41") (name "Net-(JP18-Pad2)") (class "Default")
      (node (ref "JP18") (pin "2") (pinfunction "2_2") (pintype "passive"))
      (node (ref "R8") (pin "1") (pinfunction "1_1") (pintype "passive"))
    )
    (net (code "42") (name "Net-(JP19-Pad1)") (class "Default")
      (node (ref "JP19") (pin "1") (pinfunction "1_1") (pintype "passive"))
      (node (ref "R17") (pin "2") (pinfunction "2_2") (pintype "passive"))
    )
    (net (code "43") (name "Net-(JP19-Pad2)") (class "Default")
      (node (ref "JP19") (pin "2") (pinfunction "2_2") (pintype "passive"))
      (node (ref "PB1_49") (pin "MP") (pinfunction "MP_MP") (pintype "passive"))
      (node (ref "SV9") (pin "8") (pinfunction "8_8") (pintype "passive"))
    )
    (net (code "44") (name "Net-(JP20-Pad1)") (class "Default")
      (node (ref "JP20") (pin "1") (pinfunction "1_1") (pintype "passive"))
      (node (ref "R18") (pin "2") (pinfunction "2_2") (pintype "passive"))
    )
    (net (code "45") (name "Net-(JP20-Pad2)") (class "Default")
      (node (ref "JP20") (pin "2") (pinfunction "2_2") (pintype "passive"))
      (node (ref "PB1_48") (pin "MP") (pinfunction "MP_MP") (pintype "passive"))
      (node (ref "SV9") (pin "7") (pinfunction "7_7") (pintype "passive"))
    )
    (net (code "46") (name "Net-(JP21-Pad1)") (class "Default")
      (node (ref "JP21") (pin "1") (pinfunction "1_1") (pintype "passive"))
      (node (ref "R19") (pin "2") (pinfunction "2_2") (pintype "passive"))
    )
    (net (code "47") (name "Net-(JP21-Pad2)") (class "Default")
      (node (ref "JP21") (pin "2") (pinfunction "2_2") (pintype "passive"))
      (node (ref "PB1_47") (pin "MP") (pinfunction "MP_MP") (pintype "passive"))
      (node (ref "SV9") (pin "6") (pinfunction "6_6") (pintype "passive"))
    )
    (net (code "48") (name "Net-(JP22-Pad1)") (class "Default")
      (node (ref "JP22") (pin "1") (pinfunction "1_1") (pintype "passive"))
      (node (ref "R20") (pin "2") (pinfunction "2_2") (pintype "passive"))
    )
    (net (code "49") (name "Net-(JP22-Pad2)") (class "Default")
      (node (ref "JP22") (pin "2") (pinfunction "2_2") (pintype "passive"))
      (node (ref "PB1_46") (pin "MP") (pinfunction "MP_MP") (pintype "passive"))
      (node (ref "SV9") (pin "5") (pinfunction "5_5") (pintype "passive"))
    )
    (net (code "50") (name "Net-(JP23-Pad1)") (class "Default")
      (node (ref "JP23") (pin "1") (pinfunction "1_1") (pintype "passive"))
      (node (ref "R21") (pin "2") (pinfunction "2_2") (pintype "passive"))
    )
    (net (code "51") (name "Net-(JP23-Pad2)") (class "Default")
      (node (ref "JP23") (pin "2") (pinfunction "2_2") (pintype "passive"))
      (node (ref "LSP16") (pin "MP") (pinfunction "MP_MP") (pintype "passive"))
      (node (ref "SV9") (pin "4") (pinfunction "4_4") (pintype "passive"))
    )
    (net (code "52") (name "Net-(JP24-Pad1)") (class "Default")
      (node (ref "JP24") (pin "1") (pinfunction "1_1") (pintype "passive"))
      (node (ref "R22") (pin "2") (pinfunction "2_2") (pintype "passive"))
    )
    (net (code "53") (name "Net-(JP24-Pad2)") (class "Default")
      (node (ref "JP24") (pin "2") (pinfunction "2_2") (pintype "passive"))
      (node (ref "PB1_45") (pin "MP") (pinfunction "MP_MP") (pintype "passive"))
      (node (ref "SV9") (pin "3") (pinfunction "3_3") (pintype "passive"))
    )
    (net (code "54") (name "Net-(JP25-Pad1)") (class "Default")
      (node (ref "JP25") (pin "1") (pinfunction "1_1") (pintype "passive"))
      (node (ref "R24") (pin "2") (pinfunction "2_2") (pintype "passive"))
    )
    (net (code "55") (name "Net-(JP25-Pad2)") (class "Default")
      (node (ref "JP25") (pin "2") (pinfunction "2_2") (pintype "passive"))
      (node (ref "PB1_44") (pin "MP") (pinfunction "MP_MP") (pintype "passive"))
      (node (ref "SV9") (pin "2") (pinfunction "2_2") (pintype "passive"))
    )
    (net (code "56") (name "Net-(JP26-Pad1)") (class "Default")
      (node (ref "JP26") (pin "1") (pinfunction "1_1") (pintype "passive"))
      (node (ref "R23") (pin "2") (pinfunction "2_2") (pintype "passive"))
    )
    (net (code "57") (name "Net-(JP26-Pad2)") (class "Default")
      (node (ref "JP26") (pin "2") (pinfunction "2_2") (pintype "passive"))
      (node (ref "PB1_43") (pin "MP") (pinfunction "MP_MP") (pintype "passive"))
      (node (ref "SV9") (pin "1") (pinfunction "1_1") (pintype "passive"))
    )
    (net (code "58") (name "Net-(LED1-PadA)") (class "Default")
      (node (ref "LED1") (pin "A") (pinfunction "A_A") (pintype "passive"))
      (node (ref "R9") (pin "1") (pinfunction "1_1") (pintype "passive"))
    )
    (net (code "59") (name "Net-(LED2-PadA)") (class "Default")
      (node (ref "LED2") (pin "A") (pinfunction "A_A") (pintype "passive"))
      (node (ref "R10") (pin "1") (pinfunction "1_1") (pintype "passive"))
    )
    (net (code "60") (name "Net-(LED3-PadA)") (class "Default")
      (node (ref "LED3") (pin "A") (pinfunction "A_A") (pintype "passive"))
      (node (ref "R11") (pin "1") (pinfunction "1_1") (pintype "passive"))
    )
    (net (code "61") (name "Net-(LED4-PadA)") (class "Default")
      (node (ref "LED4") (pin "A") (pinfunction "A_A") (pintype "passive"))
      (node (ref "R12") (pin "1") (pinfunction "1_1") (pintype "passive"))
    )
    (net (code "62") (name "Net-(LED5-PadA)") (class "Default")
      (node (ref "LED5") (pin "A") (pinfunction "A_A") (pintype "passive"))
      (node (ref "R13") (pin "1") (pinfunction "1_1") (pintype "passive"))
    )
    (net (code "63") (name "Net-(LED6-PadA)") (class "Default")
      (node (ref "LED6") (pin "A") (pinfunction "A_A") (pintype "passive"))
      (node (ref "R14") (pin "1") (pinfunction "1_1") (pintype "passive"))
    )
    (net (code "64") (name "Net-(LED7-PadA)") (class "Default")
      (node (ref "LED7") (pin "A") (pinfunction "A_A") (pintype "passive"))
      (node (ref "R16") (pin "1") (pinfunction "1_1") (pintype "passive"))
    )
    (net (code "65") (name "Net-(LED8-PadA)") (class "Default")
      (node (ref "LED8") (pin "A") (pinfunction "A_A") (pintype "passive"))
      (node (ref "R15") (pin "1") (pinfunction "1_1") (pintype "passive"))
    )
    (net (code "66") (name "Net-(LED9-PadA)") (class "Default")
      (node (ref "LED9") (pin "A") (pinfunction "A_A") (pintype "passive"))
      (node (ref "R2") (pin "2") (pinfunction "2_2") (pintype "passive"))
    )
    (net (code "67") (name "Net-(LED10-PadA)") (class "Default")
      (node (ref "LED10") (pin "A") (pinfunction "A_A") (pintype "passive"))
      (node (ref "R3") (pin "2") (pinfunction "2_2") (pintype "passive"))
    )
    (net (code "68") (name "Net-(LED11-PadA)") (class "Default")
      (node (ref "LED11") (pin "A") (pinfunction "A_A") (pintype "passive"))
      (node (ref "R4") (pin "2") (pinfunction "2_2") (pintype "passive"))
    )
    (net (code "69") (name "Net-(LED12-PadA)") (class "Default")
      (node (ref "LED12") (pin "A") (pinfunction "A_A") (pintype "passive"))
      (node (ref "R5") (pin "2") (pinfunction "2_2") (pintype "passive"))
    )
    (net (code "70") (name "Net-(LED13-PadA)") (class "Default")
      (node (ref "LED13") (pin "A") (pinfunction "A_A") (pintype "passive"))
      (node (ref "R6") (pin "2") (pinfunction "2_2") (pintype "passive"))
    )
    (net (code "71") (name "Net-(LED14-PadA)") (class "Default")
      (node (ref "LED14") (pin "A") (pinfunction "A_A") (pintype "passive"))
      (node (ref "R7") (pin "2") (pinfunction "2_2") (pintype "passive"))
    )
    (net (code "72") (name "Net-(LED15-PadA)") (class "Default")
      (node (ref "LED15") (pin "A") (pinfunction "A_A") (pintype "passive"))
      (node (ref "R8") (pin "2") (pinfunction "2_2") (pintype "passive"))
    )
    (net (code "73") (name "Net-(LED16-PadA)") (class "Default")
      (node (ref "LED16") (pin "A") (pinfunction "A_A") (pintype "passive"))
      (node (ref "R17") (pin "1") (pinfunction "1_1") (pintype "passive"))
    )
    (net (code "74") (name "Net-(LED17-PadA)") (class "Default")
      (node (ref "LED17") (pin "A") (pinfunction "A_A") (pintype "passive"))
      (node (ref "R18") (pin "1") (pinfunction "1_1") (pintype "passive"))
    )
    (net (code "75") (name "Net-(LED18-PadA)") (class "Default")
      (node (ref "LED18") (pin "A") (pinfunction "A_A") (pintype "passive"))
      (node (ref "R19") (pin "1") (pinfunction "1_1") (pintype "passive"))
    )
    (net (code "76") (name "Net-(LED19-PadA)") (class "Default")
      (node (ref "LED19") (pin "A") (pinfunction "A_A") (pintype "passive"))
      (node (ref "R20") (pin "1") (pinfunction "1_1") (pintype "passive"))
    )
    (net (code "77") (name "Net-(LED20-PadA)") (class "Default")
      (node (ref "LED20") (pin "A") (pinfunction "A_A") (pintype "passive"))
      (node (ref "R21") (pin "1") (pinfunction "1_1") (pintype "passive"))
    )
    (net (code "78") (name "Net-(LED21-PadA)") (class "Default")
      (node (ref "LED21") (pin "A") (pinfunction "A_A") (pintype "passive"))
      (node (ref "R22") (pin "1") (pinfunction "1_1") (pintype "passive"))
    )
    (net (code "79") (name "Net-(LED22-PadA)") (class "Default")
      (node (ref "LED22") (pin "A") (pinfunction "A_A") (pintype "passive"))
      (node (ref "R24") (pin "1") (pinfunction "1_1") (pintype "passive"))
    )
    (net (code "80") (name "Net-(LED23-PadA)") (class "Default")
      (node (ref "LED23") (pin "A") (pinfunction "A_A") (pintype "passive"))
      (node (ref "R23") (pin "1") (pinfunction "1_1") (pintype "passive"))
    )
    (net (code "81") (name "Net-(LSP3-PadMP)") (class "Default")
      (node (ref "LSP3") (pin "MP") (pinfunction "MP_MP") (pintype "passive"))
      (node (ref "LSP4") (pin "MP") (pinfunction "MP_MP") (pintype "passive"))
    )
    (net (code "82") (name "Net-(LSP8-PadMP)") (class "Default")
      (node (ref "LSP8") (pin "MP") (pinfunction "MP_MP") (pintype "passive"))
      (node (ref "PB6_IO_2") (pin "MP") (pinfunction "MP_MP") (pintype "passive"))
    )
    (net (code "83") (name "Net-(LSP10-PadMP)") (class "Default")
      (node (ref "LSP10") (pin "MP") (pinfunction "MP_MP") (pintype "passive"))
      (node (ref "SV6") (pin "3") (pinfunction "3_3") (pintype "passive"))
    )
    (net (code "84") (name "Net-(LSP12-PadMP)") (class "Default")
      (node (ref "LSP12") (pin "MP") (pinfunction "MP_MP") (pintype "passive"))
      (node (ref "LSP7") (pin "MP") (pinfunction "MP_MP") (pintype "passive"))
    )
    (net (code "85") (name "Net-(LSP13-PadMP)") (class "Default")
      (node (ref "LSP13") (pin "MP") (pinfunction "MP_MP") (pintype "passive"))
      (node (ref "PB2_4") (pin "MP") (pinfunction "MP_MP") (pintype "passive"))
    )
    (net (code "86") (name "Net-(LSP14-PadMP)") (class "Default")
      (node (ref "LSP14") (pin "MP") (pinfunction "MP_MP") (pintype "passive"))
      (node (ref "PB1_53") (pin "MP") (pinfunction "MP_MP") (pintype "passive"))
    )
    (net (code "87") (name "Net-(LSP18-PadMP)") (class "Default")
      (node (ref "LSP18") (pin "MP") (pinfunction "MP_MP") (pintype "passive"))
      (node (ref "PB1_32") (pin "MP") (pinfunction "MP_MP") (pintype "passive"))
    )
    (net (code "88") (name "Net-(LSP19-PadMP)") (class "Default")
      (node (ref "LSP19") (pin "MP") (pinfunction "MP_MP") (pintype "passive"))
      (node (ref "PB2_19") (pin "MP") (pinfunction "MP_MP") (pintype "passive"))
    )
    (net (code "89") (name "Net-(PB1_22-PadMP)") (class "Default")
      (node (ref "PB1_22") (pin "MP") (pinfunction "MP_MP") (pintype "passive"))
      (node (ref "PB2_1") (pin "MP") (pinfunction "MP_MP") (pintype "passive"))
    )
    (net (code "90") (name "Net-(PB1_23-PadMP)") (class "Default")
      (node (ref "PB1_23") (pin "MP") (pinfunction "MP_MP") (pintype "passive"))
      (node (ref "PB2_2") (pin "MP") (pinfunction "MP_MP") (pintype "passive"))
    )
    (net (code "91") (name "Net-(PB1_24-PadMP)") (class "Default")
      (node (ref "PB1_24") (pin "MP") (pinfunction "MP_MP") (pintype "passive"))
      (node (ref "PB2_3") (pin "MP") (pinfunction "MP_MP") (pintype "passive"))
    )
    (net (code "92") (name "Net-(PB1_25-PadMP)") (class "Default")
      (node (ref "PB1_25") (pin "MP") (pinfunction "MP_MP") (pintype "passive"))
      (node (ref "PB2_5") (pin "MP") (pinfunction "MP_MP") (pintype "passive"))
    )
    (net (code "93") (name "Net-(PB1_26-PadMP)") (class "Default")
      (node (ref "PB1_26") (pin "MP") (pinfunction "MP_MP") (pintype "passive"))
      (node (ref "PB2_6") (pin "MP") (pinfunction "MP_MP") (pintype "passive"))
    )
    (net (code "94") (name "Net-(PB1_27-PadMP)") (class "Default")
      (node (ref "PB1_27") (pin "MP") (pinfunction "MP_MP") (pintype "passive"))
      (node (ref "PB2_7") (pin "MP") (pinfunction "MP_MP") (pintype "passive"))
    )
    (net (code "95") (name "Net-(PB1_28-PadMP)") (class "Default")
      (node (ref "PB1_28") (pin "MP") (pinfunction "MP_MP") (pintype "passive"))
      (node (ref "PB2_8") (pin "MP") (pinfunction "MP_MP") (pintype "passive"))
    )
    (net (code "96") (name "Net-(PB1_29-PadMP)") (class "Default")
      (node (ref "PB1_29") (pin "MP") (pinfunction "MP_MP") (pintype "passive"))
      (node (ref "PB1_56") (pin "MP") (pinfunction "MP_MP") (pintype "passive"))
    )
    (net (code "97") (name "Net-(PB1_30-PadMP)") (class "Default")
      (node (ref "PB1_30") (pin "MP") (pinfunction "MP_MP") (pintype "passive"))
      (node (ref "PB1_55") (pin "MP") (pinfunction "MP_MP") (pintype "passive"))
    )
    (net (code "98") (name "Net-(PB1_31-PadMP)") (class "Default")
      (node (ref "PB1_31") (pin "MP") (pinfunction "MP_MP") (pintype "passive"))
      (node (ref "PB1_54") (pin "MP") (pinfunction "MP_MP") (pintype "passive"))
    )
    (net (code "99") (name "Net-(PB1_33-PadMP)") (class "Default")
      (node (ref "PB1_33") (pin "MP") (pinfunction "MP_MP") (pintype "passive"))
      (node (ref "PB1_52") (pin "MP") (pinfunction "MP_MP") (pintype "passive"))
    )
    (net (code "100") (name "Net-(PB1_34-PadMP)") (class "Default")
      (node (ref "PB1_34") (pin "MP") (pinfunction "MP_MP") (pintype "passive"))
      (node (ref "PB1_51") (pin "MP") (pinfunction "MP_MP") (pintype "passive"))
    )
    (net (code "101") (name "Net-(PB1_35-PadMP)") (class "Default")
      (node (ref "PB1_35") (pin "MP") (pinfunction "MP_MP") (pintype "passive"))
      (node (ref "PB1_50") (pin "MP") (pinfunction "MP_MP") (pintype "passive"))
    )
    (net (code "102") (name "Net-(PB1_57-PadMP)") (class "Default")
      (node (ref "PB1_57") (pin "MP") (pinfunction "MP_MP") (pintype "passive"))
      (node (ref "PB2_17") (pin "MP") (pinfunction "MP_MP") (pintype "passive"))
    )
    (net (code "103") (name "Net-(PB1_58-PadMP)") (class "Default")
      (node (ref "PB1_58") (pin "MP") (pinfunction "MP_MP") (pintype "passive"))
      (node (ref "PB2_18") (pin "MP") (pinfunction "MP_MP") (pintype "passive"))
    )
    (net (code "104") (name "Net-(PB1_59-PadMP)") (class "Default")
      (node (ref "PB1_59") (pin "MP") (pinfunction "MP_MP") (pintype "passive"))
      (node (ref "PB2_20") (pin "MP") (pinfunction "MP_MP") (pintype "passive"))
    )
    (net (code "105") (name "Net-(PB1_60-PadMP)") (class "Default")
      (node (ref "PB1_60") (pin "MP") (pinfunction "MP_MP") (pintype "passive"))
      (node (ref "PB2_21") (pin "MP") (pinfunction "MP_MP") (pintype "passive"))
    )
    (net (code "106") (name "Net-(PB1_61-PadMP)") (class "Default")
      (node (ref "PB1_61") (pin "MP") (pinfunction "MP_MP") (pintype "passive"))
      (node (ref "PB2_22") (pin "MP") (pinfunction "MP_MP") (pintype "passive"))
    )
    (net (code "107") (name "Net-(PB1_62-PadMP)") (class "Default")
      (node (ref "PB1_62") (pin "MP") (pinfunction "MP_MP") (pintype "passive"))
      (node (ref "PB2_23") (pin "MP") (pinfunction "MP_MP") (pintype "passive"))
    )
    (net (code "108") (name "Net-(PB6_IO_1-PadMP)") (class "Default")
      (node (ref "PB6_IO_1") (pin "MP") (pinfunction "MP_MP") (pintype "passive"))
      (node (ref "SV5") (pin "1") (pinfunction "1_1") (pintype "passive"))
    )
    (net (code "109") (name "Net-(PORT_B_1A-KL)") (class "Default")
      (node (ref "LSP5") (pin "MP") (pinfunction "MP_MP") (pintype "passive"))
      (node (ref "PB1_1") (pin "MP") (pinfunction "MP_MP") (pintype "passive"))
      (node (ref "PORT_B_1") (pin "1") (pinfunction "KL_1") (pintype "passive"))
    )
    (net (code "110") (name "Net-(PORT_B_1B-KL)") (class "Default")
      (node (ref "LSP6") (pin "MP") (pinfunction "MP_MP") (pintype "passive"))
      (node (ref "PB1_2") (pin "MP") (pinfunction "MP_MP") (pintype "passive"))
      (node (ref "PORT_B_1") (pin "2") (pinfunction "KL_2") (pintype "passive"))
    )
    (net (code "111") (name "Net-(PORT_B_1C-KL)") (class "Default")
      (node (ref "IC1") (pin "19") (pinfunction "19_19") (pintype "passive"))
      (node (ref "PB1_3") (pin "MP") (pinfunction "MP_MP") (pintype "passive"))
      (node (ref "PORT_B_1") (pin "3") (pinfunction "KL_3") (pintype "passive"))
      (node (ref "SV8") (pin "6") (pinfunction "6_6") (pintype "passive"))
      (node (ref "X1") (pin "7") (pinfunction "S_7") (pintype "passive"))
    )
    (net (code "112") (name "Net-(PORT_B_1D-KL)") (class "Default")
      (node (ref "IC1") (pin "18") (pinfunction "18_18") (pintype "passive"))
      (node (ref "LSP17") (pin "MP") (pinfunction "MP_MP") (pintype "passive"))
      (node (ref "PORT_B_1") (pin "4") (pinfunction "KL_4") (pintype "passive"))
      (node (ref "SV8") (pin "5") (pinfunction "5_5") (pintype "passive"))
      (node (ref "X1") (pin "9") (pinfunction "S_9") (pintype "passive"))
    )
    (net (code "113") (name "Net-(PORT_B_1E-KL)") (class "Default")
      (node (ref "IC1") (pin "17") (pinfunction "17_17") (pintype "passive"))
      (node (ref "PB1_5") (pin "MP") (pinfunction "MP_MP") (pintype "passive"))
      (node (ref "PORT_B_1") (pin "5") (pinfunction "KL_5") (pintype "passive"))
      (node (ref "SV8") (pin "4") (pinfunction "4_4") (pintype "passive"))
      (node (ref "X1") (pin "1") (pinfunction "S_1") (pintype "passive"))
    )
    (net (code "114") (name "Net-(PORT_B_1F-KL)") (class "Default")
      (node (ref "IC1") (pin "16") (pinfunction "16_16") (pintype "passive"))
      (node (ref "PB1_6") (pin "MP") (pinfunction "MP_MP") (pintype "passive"))
      (node (ref "PORT_B_1") (pin "6") (pinfunction "KL_6") (pintype "passive"))
      (node (ref "SV8") (pin "3") (pinfunction "3_3") (pintype "passive"))
    )
    (net (code "115") (name "Net-(PORT_B_2A-KL)") (class "Default")
      (node (ref "IC1") (pin "15") (pinfunction "15_15") (pintype "passive"))
      (node (ref "PB1_7") (pin "MP") (pinfunction "MP_MP") (pintype "passive"))
      (node (ref "PORT_B_2") (pin "1") (pinfunction "KL_1") (pintype "passive"))
      (node (ref "SV8") (pin "2") (pinfunction "2_2") (pintype "passive"))
    )
    (net (code "116") (name "Net-(PORT_B_2B-KL)") (class "Default")
      (node (ref "LSP2") (pin "MP") (pinfunction "MP_MP") (pintype "passive"))
      (node (ref "PB1_8") (pin "MP") (pinfunction "MP_MP") (pintype "passive"))
      (node (ref "PORT_B_2") (pin "2") (pinfunction "KL_2") (pintype "passive"))
      (node (ref "SV8") (pin "1") (pinfunction "1_1") (pintype "passive"))
    )
    (net (code "117") (name "Net-(PORT_C_1A-KL)") (class "Default")
      (node (ref "IC1") (pin "26") (pinfunction "26_26") (pintype "passive"))
      (node (ref "PB1_11") (pin "MP") (pinfunction "MP_MP") (pintype "passive"))
      (node (ref "PORT_C_1") (pin "1") (pinfunction "KL_1") (pintype "passive"))
    )
    (net (code "118") (name "Net-(PORT_C_1B-KL)") (class "Default")
      (node (ref "IC1") (pin "27") (pinfunction "27_27") (pintype "passive"))
      (node (ref "PB1_10") (pin "MP") (pinfunction "MP_MP") (pintype "passive"))
      (node (ref "PORT_C_1") (pin "2") (pinfunction "KL_2") (pintype "passive"))
    )
    (net (code "119") (name "Net-(PORT_C_1C-KL)") (class "Default")
      (node (ref "IC1") (pin "28") (pinfunction "28_28") (pintype "passive"))
      (node (ref "PB1_9") (pin "MP") (pinfunction "MP_MP") (pintype "passive"))
      (node (ref "PORT_C_1") (pin "3") (pinfunction "KL_3") (pintype "passive"))
    )
    (net (code "120") (name "Net-(PORT_C_1D-KL)") (class "Default")
      (node (ref "JP2") (pin "1") (pinfunction "1_1") (pintype "passive"))
      (node (ref "PORT_C_1") (pin "4") (pinfunction "KL_4") (pintype "passive"))
    )
    (net (code "121") (name "Net-(PORT_C_2A-KL)") (class "Default")
      (node (ref "IC1") (pin "23") (pinfunction "23_23") (pintype "passive"))
      (node (ref "PB1_14") (pin "MP") (pinfunction "MP_MP") (pintype "passive"))
      (node (ref "PORT_C_2") (pin "1") (pinfunction "KL_1") (pintype "passive"))
      (node (ref "SV2") (pin "2") (pinfunction "2_2") (pintype "passive"))
    )
    (net (code "122") (name "Net-(PORT_C_2B-KL)") (class "Default")
      (node (ref "IC1") (pin "24") (pinfunction "24_24") (pintype "passive"))
      (node (ref "PB1_13") (pin "MP") (pinfunction "MP_MP") (pintype "passive"))
      (node (ref "PORT_C_2") (pin "2") (pinfunction "KL_2") (pintype "passive"))
      (node (ref "SV3") (pin "2") (pinfunction "2_2") (pintype "passive"))
    )
    (net (code "123") (name "Net-(PORT_C_2C-KL)") (class "Default")
      (node (ref "IC1") (pin "25") (pinfunction "25_25") (pintype "passive"))
      (node (ref "PB1_12") (pin "MP") (pinfunction "MP_MP") (pintype "passive"))
      (node (ref "PORT_C_2") (pin "3") (pinfunction "KL_3") (pintype "passive"))
      (node (ref "SV4") (pin "2") (pinfunction "2_2") (pintype "passive"))
    )
    (net (code "124") (name "Net-(PORT_D_1A-KL)") (class "Default")
      (node (ref "IC1") (pin "2") (pinfunction "2_2") (pintype "passive"))
      (node (ref "PB1_36") (pin "MP") (pinfunction "MP_MP") (pintype "passive"))
      (node (ref "PORT_D_1") (pin "1") (pinfunction "KL_1") (pintype "passive"))
    )
    (net (code "125") (name "Net-(PORT_D_1B-KL)") (class "Default")
      (node (ref "IC1") (pin "3") (pinfunction "3_3") (pintype "passive"))
      (node (ref "PB1_37") (pin "MP") (pinfunction "MP_MP") (pintype "passive"))
      (node (ref "PORT_D_1") (pin "2") (pinfunction "KL_2") (pintype "passive"))
    )
    (net (code "126") (name "Net-(PORT_D_1C-KL)") (class "Default")
      (node (ref "IC1") (pin "4") (pinfunction "4_4") (pintype "passive"))
      (node (ref "PB1_38") (pin "MP") (pinfunction "MP_MP") (pintype "passive"))
      (node (ref "PORT_D_1") (pin "3") (pinfunction "KL_3") (pintype "passive"))
    )
    (net (code "127") (name "Net-(PORT_D_1D-KL)") (class "Default")
      (node (ref "IC1") (pin "5") (pinfunction "5_5") (pintype "passive"))
      (node (ref "LSP15") (pin "MP") (pinfunction "MP_MP") (pintype "passive"))
      (node (ref "PORT_D_1") (pin "4") (pinfunction "KL_4") (pintype "passive"))
    )
    (net (code "128") (name "Net-(PORT_D_1E-KL)") (class "Default")
      (node (ref "IC1") (pin "6") (pinfunction "6_6") (pintype "passive"))
      (node (ref "PB1_39") (pin "MP") (pinfunction "MP_MP") (pintype "passive"))
      (node (ref "PORT_D_1") (pin "5") (pinfunction "KL_5") (pintype "passive"))
    )
    (net (code "129") (name "Net-(PORT_D_1F-KL)") (class "Default")
      (node (ref "IC1") (pin "11") (pinfunction "11_11") (pintype "passive"))
      (node (ref "PB1_40") (pin "MP") (pinfunction "MP_MP") (pintype "passive"))
      (node (ref "PORT_D_1") (pin "6") (pinfunction "KL_6") (pintype "passive"))
    )
    (net (code "130") (name "Net-(PORT_D_2A-KL)") (class "Default")
      (node (ref "IC1") (pin "12") (pinfunction "12_12") (pintype "passive"))
      (node (ref "PB1_41") (pin "MP") (pinfunction "MP_MP") (pintype "passive"))
      (node (ref "PORT_D_2") (pin "1") (pinfunction "KL_1") (pintype "passive"))
    )
    (net (code "131") (name "Net-(PORT_D_2B-KL)") (class "Default")
      (node (ref "IC1") (pin "13") (pinfunction "13_13") (pintype "passive"))
      (node (ref "PB1_42") (pin "MP") (pinfunction "MP_MP") (pintype "passive"))
      (node (ref "PORT_D_2") (pin "2") (pinfunction "KL_2") (pintype "passive"))
    )
    (net (code "132") (name "Net-(X1C-S)") (class "Default")
      (node (ref "SV1") (pin "1") (pinfunction "1_1") (pintype "passive"))
      (node (ref "X1") (pin "2") (pinfunction "S_2") (pintype "passive"))
    )
    (net (code "133") (name "Net-(X1F-S)") (class "Default")
      (node (ref "IC1") (pin "1") (pinfunction "1_1") (pintype "passive"))
      (node (ref "JP1") (pin "1") (pinfunction "1_1") (pintype "passive"))
      (node (ref "JP2") (pin "2") (pinfunction "2_2") (pintype "passive"))
      (node (ref "LSP9") (pin "MP") (pinfunction "MP_MP") (pintype "passive"))
      (node (ref "X1") (pin "5") (pinfunction "S_5") (pintype "passive"))
    )
    (net (code "134") (name "Net-(X9A-KL)") (class "Default")
      (node (ref "X9") (pin "1") (pinfunction "KL_1") (pintype "passive"))
      (node (ref "X9") (pin "2") (pinfunction "KL_2") (pintype "passive"))
      (node (ref "X9") (pin "3") (pinfunction "KL_3") (pintype "passive"))
    )
    (net (code "135") (name "VCC") (class "Default")
      (node (ref "IC1") (pin "7") (pinfunction "7_7") (pintype "passive"))
      (node (ref "JP27") (pin "2") (pinfunction "2_2") (pintype "passive"))
      (node (ref "JP3") (pin "2") (pinfunction "2_2") (pintype "passive"))
      (node (ref "LSP11") (pin "MP") (pinfunction "MP_MP") (pintype "passive"))
      (node (ref "R1") (pin "2") (pinfunction "2_2") (pintype "passive"))
      (node (ref "SV1") (pin "2") (pinfunction "2_2") (pintype "passive"))
      (node (ref "SV2") (pin "3") (pinfunction "3_3") (pintype "passive"))
      (node (ref "SV3") (pin "1") (pinfunction "1_1") (pintype "passive"))
      (node (ref "SV4") (pin "1") (pinfunction "1_1") (pintype "passive"))
      (node (ref "X8") (pin "1") (pinfunction "KL_1") (pintype "passive"))
      (node (ref "X8") (pin "2") (pinfunction "KL_2") (pintype "passive"))
    )
    (net (code "136") (name "unconnected-(SV7-Pad1)") (class "Default")
      (node (ref "SV7") (pin "1") (pinfunction "1_1") (pintype "passive"))
    )
    (net (code "137") (name "unconnected-(SV7-Pad2)") (class "Default")
      (node (ref "SV7") (pin "2") (pinfunction "2_2") (pintype "passive"))
    )
    (net (code "138") (name "unconnected-(SV7-Pad3)") (class "Default")
      (node (ref "SV7") (pin "3") (pinfunction "3_3") (pintype "passive"))
    )
    (net (code "139") (name "unconnected-(SV7-Pad4)") (class "Default")
      (node (ref "SV7") (pin "4") (pinfunction "4_4") (pintype "passive"))
    )
    (net (code "140") (name "unconnected-(SV7-Pad5)") (class "Default")
      (node (ref "SV7") (pin "5") (pinfunction "5_5") (pintype "passive"))
    )
    (net (code "141") (name "unconnected-(SV7-Pad6)") (class "Default")
      (node (ref "SV7") (pin "6") (pinfunction "6_6") (pintype "passive"))
    )
    (net (code "142") (name "unconnected-(SV7-Pad7)") (class "Default")
      (node (ref "SV7") (pin "7") (pinfunction "7_7") (pintype "passive"))
    )
    (net (code "143") (name "unconnected-(X1D-S-Pad3)") (class "Default")
      (node (ref "X1") (pin "3") (pinfunction "S_3") (pintype "passive"))
    )
  )
)
